# inverter_2EDF7275K.net
KiCad netlist of a schematic drawn in Altium Designer
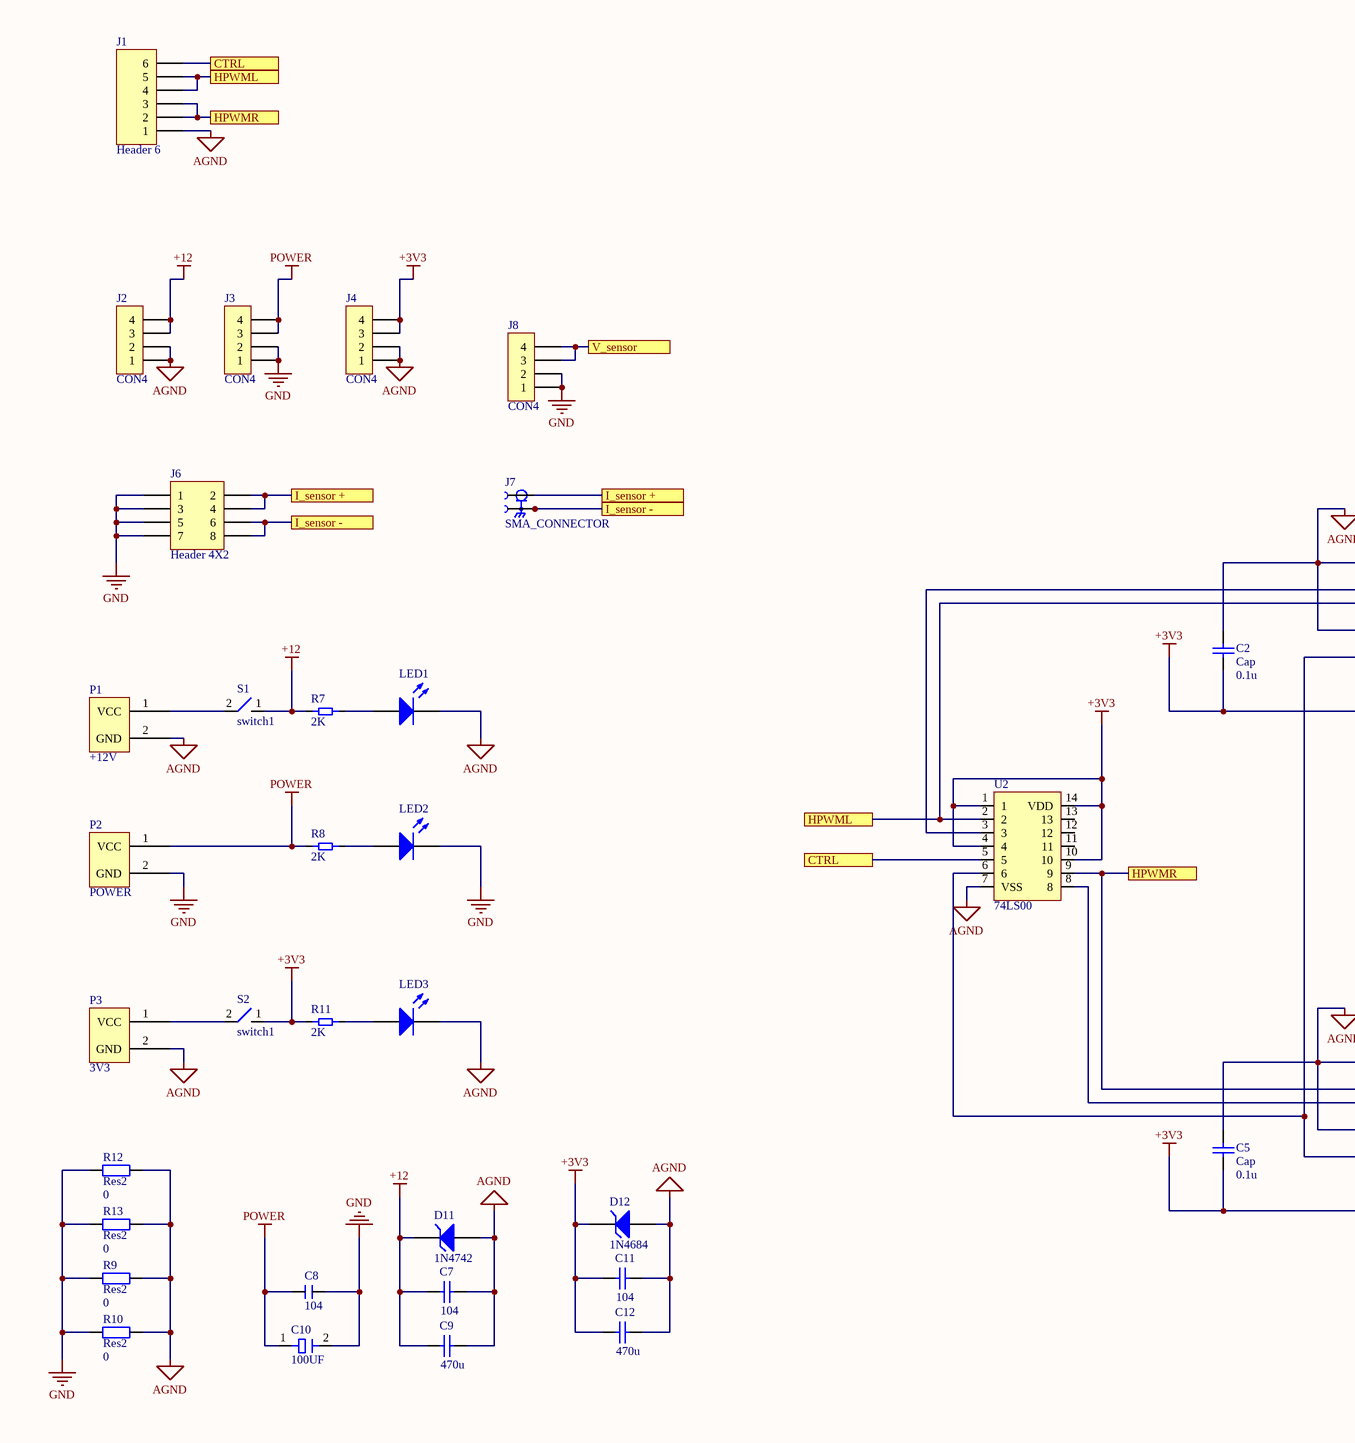
[diagram p0: inverter_2EDF7275K.SchDoc, left]
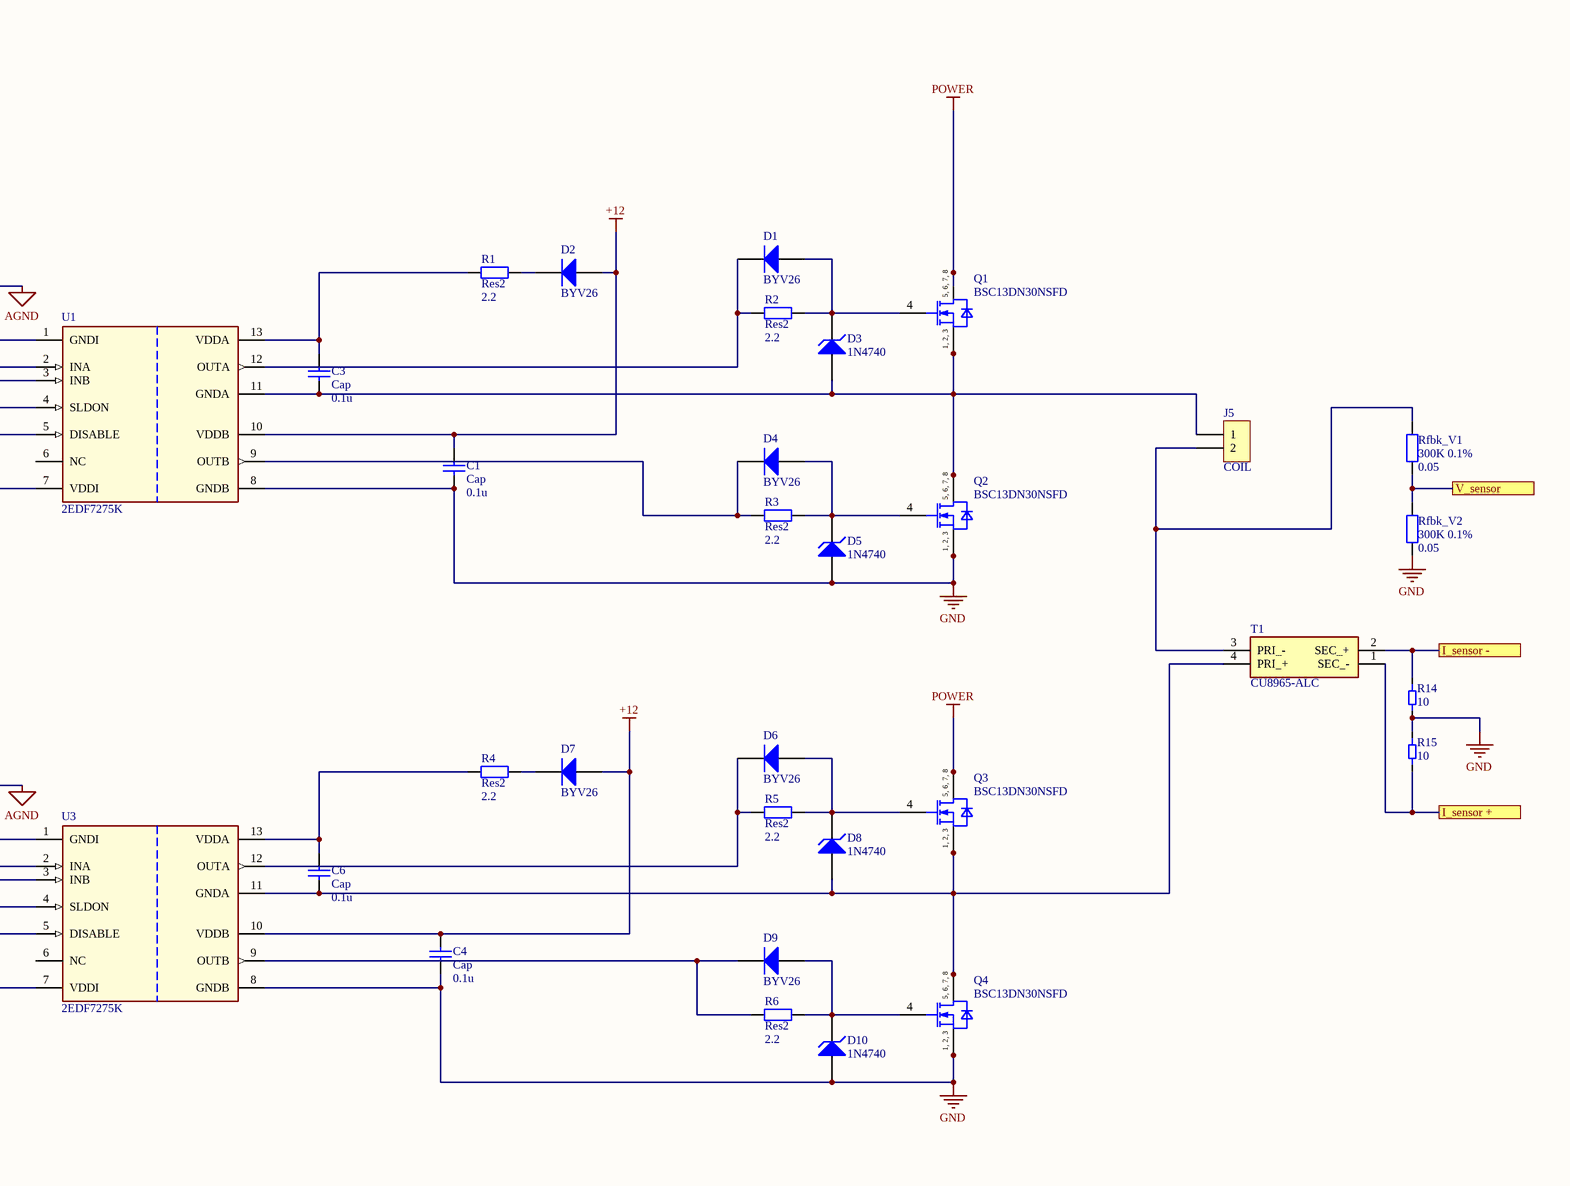
[diagram p1: inverter_2EDF7275K.SchDoc, right]

(export (version "E")
  (design (tool "Eeschema 10.0.6"))
  (components
    (comp (ref "C1")
      (value "Cap")
      (footprint "C1206")
      (description "Capacitor")
      (fields (field (name "ALTIUM_VALUE") "0.1u") (field (name "PUBLISHER") "Altium Limited"))
      (libsource (lib "Miscellaneous Devices") (part "Cap"))
    )
    (comp (ref "C2")
      (value "Cap")
      (footprint "C1206")
      (description "Capacitor")
      (fields (field (name "ALTIUM_VALUE") "0.1u") (field (name "PUBLISHER") "Altium Limited"))
      (libsource (lib "Miscellaneous Devices") (part "Cap"))
    )
    (comp (ref "C3")
      (value "Cap")
      (footprint "C1206")
      (description "Capacitor")
      (fields (field (name "ALTIUM_VALUE") "0.1u") (field (name "PUBLISHER") "Altium Limited"))
      (libsource (lib "Miscellaneous Devices") (part "Cap"))
    )
    (comp (ref "C4")
      (value "Cap")
      (footprint "C1206")
      (description "Capacitor")
      (fields (field (name "ALTIUM_VALUE") "0.1u") (field (name "PUBLISHER") "Altium Limited"))
      (libsource (lib "Miscellaneous Devices") (part "Cap"))
    )
    (comp (ref "C5")
      (value "Cap")
      (footprint "C1206")
      (description "Capacitor")
      (fields (field (name "ALTIUM_VALUE") "0.1u") (field (name "PUBLISHER") "Altium Limited"))
      (libsource (lib "Miscellaneous Devices") (part "Cap"))
    )
    (comp (ref "C6")
      (value "Cap")
      (footprint "C1206")
      (description "Capacitor")
      (fields (field (name "ALTIUM_VALUE") "0.1u") (field (name "PUBLISHER") "Altium Limited"))
      (libsource (lib "Miscellaneous Devices") (part "Cap"))
    )
    (comp (ref "C7")
      (value "104")
      (footprint "0805C")
      (description "Capacitor")
      (fields (field (name "Comment") "Cap") (field (name "PUBLISHER") "Altium Limited"))
      (libsource (lib "Miscellaneous Devices") (part "Cap"))
    )
    (comp (ref "C8") (value "104") (footprint "1210") (libsource (lib "常用") (part "CBB")))
    (comp (ref "C9")
      (value "470u")
      (footprint "CD6")
      (description "Capacitor")
      (fields (field (name "Comment") "Cap") (field (name "PUBLISHER") "Altium Limited"))
      (libsource (lib "Miscellaneous Devices") (part "Cap"))
    )
    (comp (ref "C10")
      (value "100UF")
      (footprint "CE/10MM")
      (description "电解电容")
      (libsource (lib "常用") (part "ELECTRO1"))
    )
    (comp (ref "C11")
      (value "104")
      (footprint "0805C")
      (description "Capacitor")
      (fields (field (name "Comment") "Cap") (field (name "PUBLISHER") "Altium Limited"))
      (libsource (lib "Miscellaneous Devices") (part "Cap"))
    )
    (comp (ref "C12")
      (value "470u")
      (footprint "CD6")
      (description "Capacitor")
      (fields (field (name "Comment") "Cap") (field (name "PUBLISHER") "Altium Limited"))
      (libsource (lib "Miscellaneous Devices") (part "Cap"))
    )
    (comp (ref "D1")
      (value "BYV26")
      (footprint "BYV26")
      (description "1 Amp General Purpose Rectifier")
      (fields (field (name "PUBLISHER") "Altium Limited"))
      (libsource (lib "Miscellaneous Devices") (part "Diode 1N4007"))
    )
    (comp (ref "D2")
      (value "BYV26")
      (footprint "1N4148_Stand")
      (description "1 Amp General Purpose Rectifier")
      (fields (field (name "PUBLISHER") "Altium Limited"))
      (libsource (lib "Miscellaneous Devices") (part "Diode 1N4007"))
    )
    (comp (ref "D3")
      (value "1N4740")
      (footprint "1N4148_Stand")
      (description "Zener Diode")
      (fields (field (name "PUBLISHER") "Altium Limited"))
      (libsource (lib "Miscellaneous Devices") (part "D Zener"))
    )
    (comp (ref "D4")
      (value "BYV26")
      (footprint "BYV26")
      (description "1 Amp General Purpose Rectifier")
      (fields (field (name "PUBLISHER") "Altium Limited"))
      (libsource (lib "Miscellaneous Devices") (part "Diode 1N4007"))
    )
    (comp (ref "D5")
      (value "1N4740")
      (footprint "1N4148_Stand")
      (description "Zener Diode")
      (fields (field (name "PUBLISHER") "Altium Limited"))
      (libsource (lib "Miscellaneous Devices") (part "D Zener"))
    )
    (comp (ref "D6")
      (value "BYV26")
      (footprint "BYV26")
      (description "1 Amp General Purpose Rectifier")
      (fields (field (name "PUBLISHER") "Altium Limited"))
      (libsource (lib "Miscellaneous Devices") (part "Diode 1N4007"))
    )
    (comp (ref "D7")
      (value "BYV26")
      (footprint "1N4148_Stand")
      (description "1 Amp General Purpose Rectifier")
      (fields (field (name "PUBLISHER") "Altium Limited"))
      (libsource (lib "Miscellaneous Devices") (part "Diode 1N4007"))
    )
    (comp (ref "D8")
      (value "1N4740")
      (footprint "1N4148_Stand")
      (description "Zener Diode")
      (fields (field (name "PUBLISHER") "Altium Limited"))
      (libsource (lib "Miscellaneous Devices") (part "D Zener"))
    )
    (comp (ref "D9")
      (value "BYV26")
      (footprint "BYV26")
      (description "1 Amp General Purpose Rectifier")
      (fields (field (name "PUBLISHER") "Altium Limited"))
      (libsource (lib "Miscellaneous Devices") (part "Diode 1N4007"))
    )
    (comp (ref "D10")
      (value "1N4740")
      (footprint "1N4148_Stand")
      (description "Zener Diode")
      (fields (field (name "PUBLISHER") "Altium Limited"))
      (libsource (lib "Miscellaneous Devices") (part "D Zener"))
    )
    (comp (ref "D11")
      (value "1N4742")
      (footprint "1N4148_Stand")
      (description "Zener Diode")
      (fields (field (name "PUBLISHER") "Altium Limited"))
      (libsource (lib "Miscellaneous Devices") (part "D Zener"))
    )
    (comp (ref "D12")
      (value "1N4684")
      (footprint "1N4148_Stand")
      (description "Zener Diode")
      (fields (field (name "PUBLISHER") "Altium Limited"))
      (libsource (lib "Miscellaneous Devices") (part "D Zener"))
    )
    (comp (ref "J1")
      (value "Header 6")
      (footprint "HDR1X6")
      (description "Header, 6-Pin")
      (fields (field (name "PUBLISHER") "Altium Limited"))
      (libsource (lib "Miscellaneous Connectors") (part "Header 6"))
    )
    (comp (ref "J2")
      (value "CON4")
      (footprint "SIP4")
      (description "Connector")
      (libsource (lib "插件") (part "CON4"))
    )
    (comp (ref "J3")
      (value "CON4")
      (footprint "SIP4")
      (description "Connector")
      (libsource (lib "插件") (part "CON4"))
    )
    (comp (ref "J4")
      (value "CON4")
      (footprint "SIP4")
      (description "Connector")
      (libsource (lib "插件") (part "CON4"))
    )
    (comp (ref "J5")
      (value "COIL")
      (footprint "coilnew")
      (description "Connector")
      (libsource (lib "插件") (part "CON2"))
    )
    (comp (ref "J6")
      (value "Header 4X2")
      (footprint "HDR2X4")
      (description "Header, 4-Pin, Dual row")
      (fields (field (name "PUBLISHER") "Altium Limited"))
      (libsource (lib "Miscellaneous Connectors") (part "Header 4X2"))
    )
    (comp (ref "J7")
      (value "SMA_CONNECTOR")
      (footprint "LPRS_SMA_CONNECTOR")
      (description "Straight SMA Connector")
      (libsource (lib "SMA_CONNECTOR") (part "SMA_CONNECTOR"))
    )
    (comp (ref "J8")
      (value "CON4")
      (footprint "SIP4")
      (description "Connector")
      (libsource (lib "插件") (part "CON4"))
    )
    (comp (ref "LED1")
      (value "~")
      (footprint "0603_LED")
      (description "Typical RED, GREEN, YELLOW, AMBER GaAs LED")
      (fields (field (name "PUBLISHER") "Altium Limited"))
      (libsource (lib "Miscellaneous Devices") (part "LED2"))
    )
    (comp (ref "LED2")
      (value "~")
      (footprint "0603_LED")
      (description "Typical RED, GREEN, YELLOW, AMBER GaAs LED")
      (fields (field (name "PUBLISHER") "Altium Limited"))
      (libsource (lib "Miscellaneous Devices") (part "LED2"))
    )
    (comp (ref "LED3")
      (value "~")
      (footprint "0603_LED")
      (description "Typical RED, GREEN, YELLOW, AMBER GaAs LED")
      (fields (field (name "PUBLISHER") "Altium Limited"))
      (libsource (lib "Miscellaneous Devices") (part "LED2"))
    )
    (comp (ref "P1") (value "+12V") (footprint "050-2") (libsource (lib "常用") (part "POWER")))
    (comp (ref "P2") (value "POWER") (footprint "050-2") (libsource (lib "常用") (part "POWER")))
    (comp (ref "P3") (value "3V3") (footprint "050-2") (libsource (lib "常用") (part "POWER")))
    (comp (ref "Q1")
      (value "BSC13DN30NSFD")
      (footprint "IFX-PG-TDSON-8-V")
      (fields (field (name "MANUFACTURER") "Infineon Technologies"))
      (libsource (lib "BSC13DN30NSFD") (part "BSC13DN30NSFD"))
    )
    (comp (ref "Q2")
      (value "BSC13DN30NSFD")
      (footprint "IFX-PG-TDSON-8-V")
      (fields (field (name "MANUFACTURER") "Infineon Technologies"))
      (libsource (lib "BSC13DN30NSFD") (part "BSC13DN30NSFD"))
    )
    (comp (ref "Q3")
      (value "BSC13DN30NSFD")
      (footprint "IFX-PG-TDSON-8-V")
      (fields (field (name "MANUFACTURER") "Infineon Technologies"))
      (libsource (lib "BSC13DN30NSFD") (part "BSC13DN30NSFD"))
    )
    (comp (ref "Q4")
      (value "BSC13DN30NSFD")
      (footprint "IFX-PG-TDSON-8-V")
      (fields (field (name "MANUFACTURER") "Infineon Technologies"))
      (libsource (lib "BSC13DN30NSFD") (part "BSC13DN30NSFD"))
    )
    (comp (ref "R1")
      (value "Res2")
      (footprint "0805R")
      (description "Resistor")
      (fields (field (name "ALTIUM_VALUE") "2.2") (field (name "PUBLISHER") "Altium Limited"))
      (libsource (lib "Miscellaneous Devices") (part "Res2"))
    )
    (comp (ref "R2")
      (value "Res2")
      (footprint "0805R")
      (description "Resistor")
      (fields (field (name "ALTIUM_VALUE") "2.2") (field (name "PUBLISHER") "Altium Limited"))
      (libsource (lib "Miscellaneous Devices") (part "Res2"))
    )
    (comp (ref "R3")
      (value "Res2")
      (footprint "0805R")
      (description "Resistor")
      (fields (field (name "ALTIUM_VALUE") "2.2") (field (name "PUBLISHER") "Altium Limited"))
      (libsource (lib "Miscellaneous Devices") (part "Res2"))
    )
    (comp (ref "R4")
      (value "Res2")
      (footprint "0805R")
      (description "Resistor")
      (fields (field (name "ALTIUM_VALUE") "2.2") (field (name "PUBLISHER") "Altium Limited"))
      (libsource (lib "Miscellaneous Devices") (part "Res2"))
    )
    (comp (ref "R5")
      (value "Res2")
      (footprint "0805R")
      (description "Resistor")
      (fields (field (name "ALTIUM_VALUE") "2.2") (field (name "PUBLISHER") "Altium Limited"))
      (libsource (lib "Miscellaneous Devices") (part "Res2"))
    )
    (comp (ref "R6")
      (value "Res2")
      (footprint "0805R")
      (description "Resistor")
      (fields (field (name "ALTIUM_VALUE") "2.2") (field (name "PUBLISHER") "Altium Limited"))
      (libsource (lib "Miscellaneous Devices") (part "Res2"))
    )
    (comp (ref "R7") (value "2K") (footprint "0603-R") (libsource (lib "常用") (part "RES")))
    (comp (ref "R8") (value "2K") (footprint "0603-R") (libsource (lib "常用") (part "RES")))
    (comp (ref "R9")
      (value "Res2")
      (footprint "1206R")
      (description "Resistor")
      (fields (field (name "ALTIUM_VALUE") "0") (field (name "PUBLISHER") "Altium Limited"))
      (libsource (lib "Miscellaneous Devices") (part "Res2"))
    )
    (comp (ref "R10")
      (value "Res2")
      (footprint "1206R")
      (description "Resistor")
      (fields (field (name "ALTIUM_VALUE") "0") (field (name "PUBLISHER") "Altium Limited"))
      (libsource (lib "Miscellaneous Devices") (part "Res2"))
    )
    (comp (ref "R11") (value "2K") (footprint "0603-R") (libsource (lib "常用") (part "RES")))
    (comp (ref "R12")
      (value "Res2")
      (footprint "1206R")
      (description "Resistor")
      (fields (field (name "ALTIUM_VALUE") "0") (field (name "PUBLISHER") "Altium Limited"))
      (libsource (lib "Miscellaneous Devices") (part "Res2"))
    )
    (comp (ref "R13")
      (value "Res2")
      (footprint "1206R")
      (description "Resistor")
      (fields (field (name "ALTIUM_VALUE") "0") (field (name "PUBLISHER") "Altium Limited"))
      (libsource (lib "Miscellaneous Devices") (part "Res2"))
    )
    (comp (ref "R14") (value "10") (footprint "AXIAL0.3") (libsource (lib "常用") (part "RES")))
    (comp (ref "R15") (value "10") (footprint "AXIAL0.3") (libsource (lib "常用") (part "RES")))
    (comp (ref "Rfbk_V1")
      (value "300K 0.1%")
      (footprint "AXIAL0.3")
      (description "Resistor")
      (fields (field (name "ALTIUM_VALUE") "0.05") (field (name "PUBLISHER") "Altium Limited"))
      (libsource (lib "") (part "Res2_1"))
    )
    (comp (ref "Rfbk_V2")
      (value "300K 0.1%")
      (footprint "AXIAL0.3")
      (description "Resistor")
      (fields (field (name "ALTIUM_VALUE") "0.05") (field (name "PUBLISHER") "Altium Limited"))
      (libsource (lib "") (part "Res2_1"))
    )
    (comp (ref "S1") (value "switch1") (footprint "Switch_8.2*5.2") (libsource (lib "常用") (part "switch1")))
    (comp (ref "S2") (value "switch1") (footprint "Switch_8.2*5.2") (libsource (lib "常用") (part "switch1")))
    (comp (ref "T1")
      (value "CU8965-ALC")
      (footprint "CU8965ALD")
      (description "Transformer")
      (libsource (lib "CU8965") (part "CU8965-ALC"))
    )
    (comp (ref "U1")
      (value "2EDF7275K")
      (footprint "TFLGA65P500X500X106-14_13N-V")
      (description "Dual-Channel, Functional and Reinforced Isolated MOSFET Gate-Driver")
      (libsource (lib "2EDF7275K") (part "2EDF7275K"))
    )
    (comp (ref "U2") (value "74LS00") (footprint "74ls00") (libsource (lib "常用") (part "74LS00")))
    (comp (ref "U3")
      (value "2EDF7275K")
      (footprint "TFLGA65P500X500X106-14_13N-V")
      (description "Dual-Channel, Functional and Reinforced Isolated MOSFET Gate-Driver")
      (libsource (lib "2EDF7275K") (part "2EDF7275K"))
    )
  )
  (nets
    (net (code "1") (name "+3V3") (class "Default")
      (node (ref "C11") (pin "1") (pinfunction "1_1") (pintype "passive"))
      (node (ref "C12") (pin "1") (pinfunction "1_1") (pintype "passive"))
      (node (ref "C2") (pin "1") (pinfunction "1_1") (pintype "passive"))
      (node (ref "C5") (pin "1") (pinfunction "1_1") (pintype "passive"))
      (node (ref "D12") (pin "2") (pinfunction "K_2") (pintype "passive"))
      (node (ref "J4") (pin "3") (pinfunction "3_3") (pintype "passive"))
      (node (ref "J4") (pin "4") (pinfunction "4_4") (pintype "passive"))
      (node (ref "R11") (pin "2") (pinfunction "2_2") (pintype "passive"))
      (node (ref "S2") (pin "1") (pinfunction "1_1") (pintype "passive"))
      (node (ref "U1") (pin "7") (pinfunction "VDDI_7") (pintype "power_in"))
      (node (ref "U2") (pin "1") (pinfunction "1_1") (pintype "passive"))
      (node (ref "U2") (pin "10") (pinfunction "10_10") (pintype "passive"))
      (node (ref "U2") (pin "14") (pinfunction "VDD_14") (pintype "passive"))
      (node (ref "U2") (pin "4") (pinfunction "4_4") (pintype "passive"))
      (node (ref "U3") (pin "7") (pinfunction "VDDI_7") (pintype "power_in"))
    )
    (net (code "2") (name "+12") (class "Default")
      (node (ref "C1") (pin "2") (pinfunction "2_2") (pintype "passive"))
      (node (ref "C4") (pin "2") (pinfunction "2_2") (pintype "passive"))
      (node (ref "C7") (pin "1") (pinfunction "1_1") (pintype "passive"))
      (node (ref "C9") (pin "1") (pinfunction "1_1") (pintype "passive"))
      (node (ref "D11") (pin "2") (pinfunction "K_2") (pintype "passive"))
      (node (ref "D2") (pin "1") (pinfunction "A_1") (pintype "passive"))
      (node (ref "D7") (pin "1") (pinfunction "A_1") (pintype "passive"))
      (node (ref "J2") (pin "3") (pinfunction "3_3") (pintype "passive"))
      (node (ref "J2") (pin "4") (pinfunction "4_4") (pintype "passive"))
      (node (ref "R7") (pin "2") (pinfunction "2_2") (pintype "passive"))
      (node (ref "S1") (pin "1") (pinfunction "1_1") (pintype "passive"))
      (node (ref "U1") (pin "10") (pinfunction "VDDB_10") (pintype "power_in"))
      (node (ref "U3") (pin "10") (pinfunction "VDDB_10") (pintype "power_in"))
    )
    (net (code "3") (name "/CTRL") (class "Default")
      (node (ref "J1") (pin "6") (pinfunction "6_6") (pintype "passive"))
      (node (ref "U2") (pin "5") (pinfunction "5_5") (pintype "passive"))
    )
    (net (code "4") (name "/HPWML") (class "Default")
      (node (ref "J1") (pin "4") (pinfunction "4_4") (pintype "passive"))
      (node (ref "J1") (pin "5") (pinfunction "5_5") (pintype "passive"))
      (node (ref "U1") (pin "3") (pinfunction "INB_3") (pintype "input"))
      (node (ref "U2") (pin "2") (pinfunction "2_2") (pintype "passive"))
    )
    (net (code "5") (name "/HPWMR") (class "Default")
      (node (ref "J1") (pin "2") (pinfunction "2_2") (pintype "passive"))
      (node (ref "J1") (pin "3") (pinfunction "3_3") (pintype "passive"))
      (node (ref "U2") (pin "9") (pinfunction "9_9") (pintype "passive"))
      (node (ref "U3") (pin "2") (pinfunction "INA_2") (pintype "input"))
    )
    (net (code "6") (name "/I_sensor +") (class "Default")
      (node (ref "J6") (pin "2") (pinfunction "2_2") (pintype "passive"))
      (node (ref "J6") (pin "4") (pinfunction "4_4") (pintype "passive"))
      (node (ref "J7") (pin "1") (pinfunction "1_1") (pintype "passive"))
      (node (ref "R15") (pin "2") (pinfunction "2_2") (pintype "passive"))
      (node (ref "T1") (pin "1") (pinfunction "SEC_-_1") (pintype "passive"))
    )
    (net (code "7") (name "/I_sensor -") (class "Default")
      (node (ref "J6") (pin "6") (pinfunction "6_6") (pintype "passive"))
      (node (ref "J6") (pin "8") (pinfunction "8_8") (pintype "passive"))
      (node (ref "J7") (pin "G1") (pinfunction "2_G1") (pintype "passive"))
      (node (ref "J7") (pin "G2") (pinfunction "2_G2") (pintype "passive"))
      (node (ref "J7") (pin "G3") (pinfunction "2_G3") (pintype "passive"))
      (node (ref "J7") (pin "G4") (pinfunction "2_G4") (pintype "passive"))
      (node (ref "R14") (pin "1") (pinfunction "1_1") (pintype "passive"))
      (node (ref "T1") (pin "2") (pinfunction "SEC_+_2") (pintype "passive"))
    )
    (net (code "8") (name "/V_sensor") (class "Default")
      (node (ref "J8") (pin "3") (pinfunction "3_3") (pintype "passive"))
      (node (ref "J8") (pin "4") (pinfunction "4_4") (pintype "passive"))
      (node (ref "Rfbk_V1") (pin "1") (pinfunction "1_1") (pintype "passive"))
      (node (ref "Rfbk_V2") (pin "2") (pinfunction "2_2") (pintype "passive"))
    )
    (net (code "9") (name "AGND") (class "Default")
      (node (ref "C11") (pin "2") (pinfunction "2_2") (pintype "passive"))
      (node (ref "C12") (pin "2") (pinfunction "2_2") (pintype "passive"))
      (node (ref "C2") (pin "2") (pinfunction "2_2") (pintype "passive"))
      (node (ref "C5") (pin "2") (pinfunction "2_2") (pintype "passive"))
      (node (ref "C7") (pin "2") (pinfunction "2_2") (pintype "passive"))
      (node (ref "C9") (pin "2") (pinfunction "2_2") (pintype "passive"))
      (node (ref "D11") (pin "1") (pinfunction "A_1") (pintype "passive"))
      (node (ref "D12") (pin "1") (pinfunction "A_1") (pintype "passive"))
      (node (ref "J1") (pin "1") (pinfunction "1_1") (pintype "passive"))
      (node (ref "J2") (pin "1") (pinfunction "1_1") (pintype "passive"))
      (node (ref "J2") (pin "2") (pinfunction "2_2") (pintype "passive"))
      (node (ref "J4") (pin "1") (pinfunction "1_1") (pintype "passive"))
      (node (ref "J4") (pin "2") (pinfunction "2_2") (pintype "passive"))
      (node (ref "LED1") (pin "2") (pinfunction "K_2") (pintype "passive"))
      (node (ref "LED3") (pin "2") (pinfunction "K_2") (pintype "passive"))
      (node (ref "P1") (pin "2") (pinfunction "GND_2") (pintype "passive"))
      (node (ref "P3") (pin "2") (pinfunction "GND_2") (pintype "passive"))
      (node (ref "R10") (pin "2") (pinfunction "2_2") (pintype "passive"))
      (node (ref "R12") (pin "2") (pinfunction "2_2") (pintype "passive"))
      (node (ref "R13") (pin "2") (pinfunction "2_2") (pintype "passive"))
      (node (ref "R9") (pin "2") (pinfunction "2_2") (pintype "passive"))
      (node (ref "U1") (pin "1") (pinfunction "GNDI_1") (pintype "power_in"))
      (node (ref "U1") (pin "4") (pinfunction "SLDON_4") (pintype "input"))
      (node (ref "U2") (pin "7") (pinfunction "VSS_7") (pintype "passive"))
      (node (ref "U3") (pin "1") (pinfunction "GNDI_1") (pintype "power_in"))
      (node (ref "U3") (pin "4") (pinfunction "SLDON_4") (pintype "input"))
    )
    (net (code "10") (name "GND") (class "Default")
      (node (ref "C1") (pin "1") (pinfunction "1_1") (pintype "passive"))
      (node (ref "C10") (pin "2") (pinfunction "2_2") (pintype "passive"))
      (node (ref "C4") (pin "1") (pinfunction "1_1") (pintype "passive"))
      (node (ref "C8") (pin "2") (pinfunction "2_2") (pintype "power_in"))
      (node (ref "D10") (pin "1") (pinfunction "A_1") (pintype "passive"))
      (node (ref "D5") (pin "1") (pinfunction "A_1") (pintype "passive"))
      (node (ref "J3") (pin "1") (pinfunction "1_1") (pintype "passive"))
      (node (ref "J3") (pin "2") (pinfunction "2_2") (pintype "passive"))
      (node (ref "J6") (pin "1") (pinfunction "1_1") (pintype "passive"))
      (node (ref "J6") (pin "3") (pinfunction "3_3") (pintype "passive"))
      (node (ref "J6") (pin "5") (pinfunction "5_5") (pintype "passive"))
      (node (ref "J6") (pin "7") (pinfunction "7_7") (pintype "passive"))
      (node (ref "J8") (pin "1") (pinfunction "1_1") (pintype "passive"))
      (node (ref "J8") (pin "2") (pinfunction "2_2") (pintype "passive"))
      (node (ref "LED2") (pin "2") (pinfunction "K_2") (pintype "passive"))
      (node (ref "P2") (pin "2") (pinfunction "GND_2") (pintype "passive"))
      (node (ref "Q2") (pin "1") (pinfunction "SOURCE_1") (pintype "passive"))
      (node (ref "Q2") (pin "2") (pinfunction "SOURCE_2") (pintype "passive"))
      (node (ref "Q2") (pin "3") (pinfunction "SOURCE_3") (pintype "passive"))
      (node (ref "Q4") (pin "1") (pinfunction "SOURCE_1") (pintype "passive"))
      (node (ref "Q4") (pin "2") (pinfunction "SOURCE_2") (pintype "passive"))
      (node (ref "Q4") (pin "3") (pinfunction "SOURCE_3") (pintype "passive"))
      (node (ref "R10") (pin "1") (pinfunction "1_1") (pintype "passive"))
      (node (ref "R12") (pin "1") (pinfunction "1_1") (pintype "passive"))
      (node (ref "R13") (pin "1") (pinfunction "1_1") (pintype "passive"))
      (node (ref "R14") (pin "2") (pinfunction "2_2") (pintype "passive"))
      (node (ref "R15") (pin "1") (pinfunction "1_1") (pintype "passive"))
      (node (ref "R9") (pin "1") (pinfunction "1_1") (pintype "passive"))
      (node (ref "Rfbk_V2") (pin "1") (pinfunction "1_1") (pintype "passive"))
      (node (ref "U1") (pin "8") (pinfunction "GNDB_8") (pintype "power_in"))
      (node (ref "U3") (pin "8") (pinfunction "GNDB_8") (pintype "power_in"))
    )
    (net (code "11") (name "Net-(D1-A)") (class "Default")
      (node (ref "D1") (pin "1") (pinfunction "A_1") (pintype "passive"))
      (node (ref "D3") (pin "2") (pinfunction "K_2") (pintype "passive"))
      (node (ref "Q1") (pin "4") (pinfunction "GATE_4") (pintype "passive"))
      (node (ref "R2") (pin "2") (pinfunction "2_2") (pintype "passive"))
    )
    (net (code "12") (name "Net-(D1-K)") (class "Default")
      (node (ref "D1") (pin "2") (pinfunction "K_2") (pintype "passive"))
      (node (ref "R2") (pin "1") (pinfunction "1_1") (pintype "passive"))
      (node (ref "U1") (pin "12") (pinfunction "OUTA_12") (pintype "output"))
    )
    (net (code "13") (name "Net-(D2-K)") (class "Default")
      (node (ref "D2") (pin "2") (pinfunction "K_2") (pintype "passive"))
      (node (ref "R1") (pin "2") (pinfunction "2_2") (pintype "passive"))
    )
    (net (code "14") (name "Net-(D3-A)") (class "Default")
      (node (ref "C3") (pin "1") (pinfunction "1_1") (pintype "passive"))
      (node (ref "D3") (pin "1") (pinfunction "A_1") (pintype "passive"))
      (node (ref "J5") (pin "1") (pinfunction "1_1") (pintype "passive"))
      (node (ref "Q1") (pin "1") (pinfunction "SOURCE_1") (pintype "passive"))
      (node (ref "Q1") (pin "2") (pinfunction "SOURCE_2") (pintype "passive"))
      (node (ref "Q1") (pin "3") (pinfunction "SOURCE_3") (pintype "passive"))
      (node (ref "Q2") (pin "5") (pinfunction "DRAIN_5") (pintype "passive"))
      (node (ref "Q2") (pin "6") (pinfunction "DRAIN_6") (pintype "passive"))
      (node (ref "Q2") (pin "7") (pinfunction "DRAIN_7") (pintype "passive"))
      (node (ref "Q2") (pin "8") (pinfunction "DRAIN_8") (pintype "passive"))
      (node (ref "U1") (pin "11") (pinfunction "GNDA_11") (pintype "power_in"))
    )
    (net (code "15") (name "Net-(D4-A)") (class "Default")
      (node (ref "D4") (pin "1") (pinfunction "A_1") (pintype "passive"))
      (node (ref "D5") (pin "2") (pinfunction "K_2") (pintype "passive"))
      (node (ref "Q2") (pin "4") (pinfunction "GATE_4") (pintype "passive"))
      (node (ref "R3") (pin "2") (pinfunction "2_2") (pintype "passive"))
    )
    (net (code "16") (name "Net-(D4-K)") (class "Default")
      (node (ref "D4") (pin "2") (pinfunction "K_2") (pintype "passive"))
      (node (ref "R3") (pin "1") (pinfunction "1_1") (pintype "passive"))
      (node (ref "U1") (pin "9") (pinfunction "OUTB_9") (pintype "output"))
    )
    (net (code "17") (name "Net-(D6-A)") (class "Default")
      (node (ref "D6") (pin "1") (pinfunction "A_1") (pintype "passive"))
      (node (ref "D8") (pin "2") (pinfunction "K_2") (pintype "passive"))
      (node (ref "Q3") (pin "4") (pinfunction "GATE_4") (pintype "passive"))
      (node (ref "R5") (pin "2") (pinfunction "2_2") (pintype "passive"))
    )
    (net (code "18") (name "Net-(D6-K)") (class "Default")
      (node (ref "D6") (pin "2") (pinfunction "K_2") (pintype "passive"))
      (node (ref "R5") (pin "1") (pinfunction "1_1") (pintype "passive"))
      (node (ref "U3") (pin "12") (pinfunction "OUTA_12") (pintype "output"))
    )
    (net (code "19") (name "Net-(D7-K)") (class "Default")
      (node (ref "D7") (pin "2") (pinfunction "K_2") (pintype "passive"))
      (node (ref "R4") (pin "2") (pinfunction "2_2") (pintype "passive"))
    )
    (net (code "20") (name "Net-(D8-A)") (class "Default")
      (node (ref "C6") (pin "1") (pinfunction "1_1") (pintype "passive"))
      (node (ref "D8") (pin "1") (pinfunction "A_1") (pintype "passive"))
      (node (ref "Q3") (pin "1") (pinfunction "SOURCE_1") (pintype "passive"))
      (node (ref "Q3") (pin "2") (pinfunction "SOURCE_2") (pintype "passive"))
      (node (ref "Q3") (pin "3") (pinfunction "SOURCE_3") (pintype "passive"))
      (node (ref "Q4") (pin "5") (pinfunction "DRAIN_5") (pintype "passive"))
      (node (ref "Q4") (pin "6") (pinfunction "DRAIN_6") (pintype "passive"))
      (node (ref "Q4") (pin "7") (pinfunction "DRAIN_7") (pintype "passive"))
      (node (ref "Q4") (pin "8") (pinfunction "DRAIN_8") (pintype "passive"))
      (node (ref "T1") (pin "4") (pinfunction "PRI_+_4") (pintype "passive"))
      (node (ref "U3") (pin "11") (pinfunction "GNDA_11") (pintype "power_in"))
    )
    (net (code "21") (name "Net-(D9-K)") (class "Default")
      (node (ref "D9") (pin "2") (pinfunction "K_2") (pintype "passive"))
      (node (ref "R6") (pin "1") (pinfunction "1_1") (pintype "passive"))
      (node (ref "U3") (pin "9") (pinfunction "OUTB_9") (pintype "output"))
    )
    (net (code "22") (name "Net-(D10-K)") (class "Default")
      (node (ref "D10") (pin "2") (pinfunction "K_2") (pintype "passive"))
      (node (ref "D9") (pin "1") (pinfunction "A_1") (pintype "passive"))
      (node (ref "Q4") (pin "4") (pinfunction "GATE_4") (pintype "passive"))
      (node (ref "R6") (pin "2") (pinfunction "2_2") (pintype "passive"))
    )
    (net (code "23") (name "Net-(LED1-A)") (class "Default")
      (node (ref "LED1") (pin "1") (pinfunction "A_1") (pintype "passive"))
      (node (ref "R7") (pin "1") (pinfunction "1_1") (pintype "passive"))
    )
    (net (code "24") (name "Net-(LED2-A)") (class "Default")
      (node (ref "LED2") (pin "1") (pinfunction "A_1") (pintype "passive"))
      (node (ref "R8") (pin "1") (pinfunction "1_1") (pintype "passive"))
    )
    (net (code "25") (name "Net-(LED3-A)") (class "Default")
      (node (ref "LED3") (pin "1") (pinfunction "A_1") (pintype "passive"))
      (node (ref "R11") (pin "1") (pinfunction "1_1") (pintype "passive"))
    )
    (net (code "26") (name "Net-(P1-VCC)") (class "Default")
      (node (ref "P1") (pin "1") (pinfunction "VCC_1") (pintype "passive"))
      (node (ref "S1") (pin "2") (pinfunction "2_2") (pintype "passive"))
    )
    (net (code "27") (name "Net-(P3-VCC)") (class "Default")
      (node (ref "P3") (pin "1") (pinfunction "VCC_1") (pintype "passive"))
      (node (ref "S2") (pin "2") (pinfunction "2_2") (pintype "passive"))
    )
    (net (code "28") (name "Net-(T1-PRI_-)") (class "Default")
      (node (ref "J5") (pin "2") (pinfunction "2_2") (pintype "passive"))
      (node (ref "Rfbk_V1") (pin "2") (pinfunction "2_2") (pintype "passive"))
      (node (ref "T1") (pin "3") (pinfunction "PRI_-_3") (pintype "passive"))
    )
    (net (code "29") (name "Net-(U1-DISABLE)") (class "Default")
      (node (ref "U1") (pin "5") (pinfunction "DISABLE_5") (pintype "input"))
      (node (ref "U2") (pin "6") (pinfunction "6_6") (pintype "passive"))
      (node (ref "U3") (pin "5") (pinfunction "DISABLE_5") (pintype "input"))
    )
    (net (code "30") (name "Net-(U1-INA)") (class "Default")
      (node (ref "U1") (pin "2") (pinfunction "INA_2") (pintype "input"))
      (node (ref "U2") (pin "3") (pinfunction "3_3") (pintype "passive"))
    )
    (net (code "31") (name "Net-(U1-VDDA)") (class "Default")
      (node (ref "C3") (pin "2") (pinfunction "2_2") (pintype "passive"))
      (node (ref "R1") (pin "1") (pinfunction "1_1") (pintype "passive"))
      (node (ref "U1") (pin "13") (pinfunction "VDDA_13") (pintype "power_in"))
    )
    (net (code "32") (name "Net-(U3-INB)") (class "Default")
      (node (ref "U2") (pin "8") (pinfunction "8_8") (pintype "passive"))
      (node (ref "U3") (pin "3") (pinfunction "INB_3") (pintype "input"))
    )
    (net (code "33") (name "Net-(U3-VDDA)") (class "Default")
      (node (ref "C6") (pin "2") (pinfunction "2_2") (pintype "passive"))
      (node (ref "R4") (pin "1") (pinfunction "1_1") (pintype "passive"))
      (node (ref "U3") (pin "13") (pinfunction "VDDA_13") (pintype "power_in"))
    )
    (net (code "34") (name "POWER") (class "Default")
      (node (ref "C10") (pin "1") (pinfunction "1_1") (pintype "passive"))
      (node (ref "C8") (pin "1") (pinfunction "1_1") (pintype "passive"))
      (node (ref "J3") (pin "3") (pinfunction "3_3") (pintype "passive"))
      (node (ref "J3") (pin "4") (pinfunction "4_4") (pintype "passive"))
      (node (ref "P2") (pin "1") (pinfunction "VCC_1") (pintype "passive"))
      (node (ref "Q1") (pin "5") (pinfunction "DRAIN_5") (pintype "passive"))
      (node (ref "Q1") (pin "6") (pinfunction "DRAIN_6") (pintype "passive"))
      (node (ref "Q1") (pin "7") (pinfunction "DRAIN_7") (pintype "passive"))
      (node (ref "Q1") (pin "8") (pinfunction "DRAIN_8") (pintype "passive"))
      (node (ref "Q3") (pin "5") (pinfunction "DRAIN_5") (pintype "passive"))
      (node (ref "Q3") (pin "6") (pinfunction "DRAIN_6") (pintype "passive"))
      (node (ref "Q3") (pin "7") (pinfunction "DRAIN_7") (pintype "passive"))
      (node (ref "Q3") (pin "8") (pinfunction "DRAIN_8") (pintype "passive"))
      (node (ref "R8") (pin "2") (pinfunction "2_2") (pintype "passive"))
    )
    (net (code "35") (name "unconnected-(U1-NC-Pad6)") (class "Default")
      (node (ref "U1") (pin "6") (pinfunction "NC_6") (pintype "passive"))
    )
    (net (code "36") (name "unconnected-(U2-Pad11)") (class "Default")
      (node (ref "U2") (pin "11") (pinfunction "11_11") (pintype "passive"))
    )
    (net (code "37") (name "unconnected-(U2-Pad12)") (class "Default")
      (node (ref "U2") (pin "12") (pinfunction "12_12") (pintype "passive"))
    )
    (net (code "38") (name "unconnected-(U2-Pad13)") (class "Default")
      (node (ref "U2") (pin "13") (pinfunction "13_13") (pintype "passive"))
    )
    (net (code "39") (name "unconnected-(U3-NC-Pad6)") (class "Default")
      (node (ref "U3") (pin "6") (pinfunction "NC_6") (pintype "passive"))
    )
  )
)
